# touringmach0.net
KiCad netlist of a schematic drawn in EAGLE
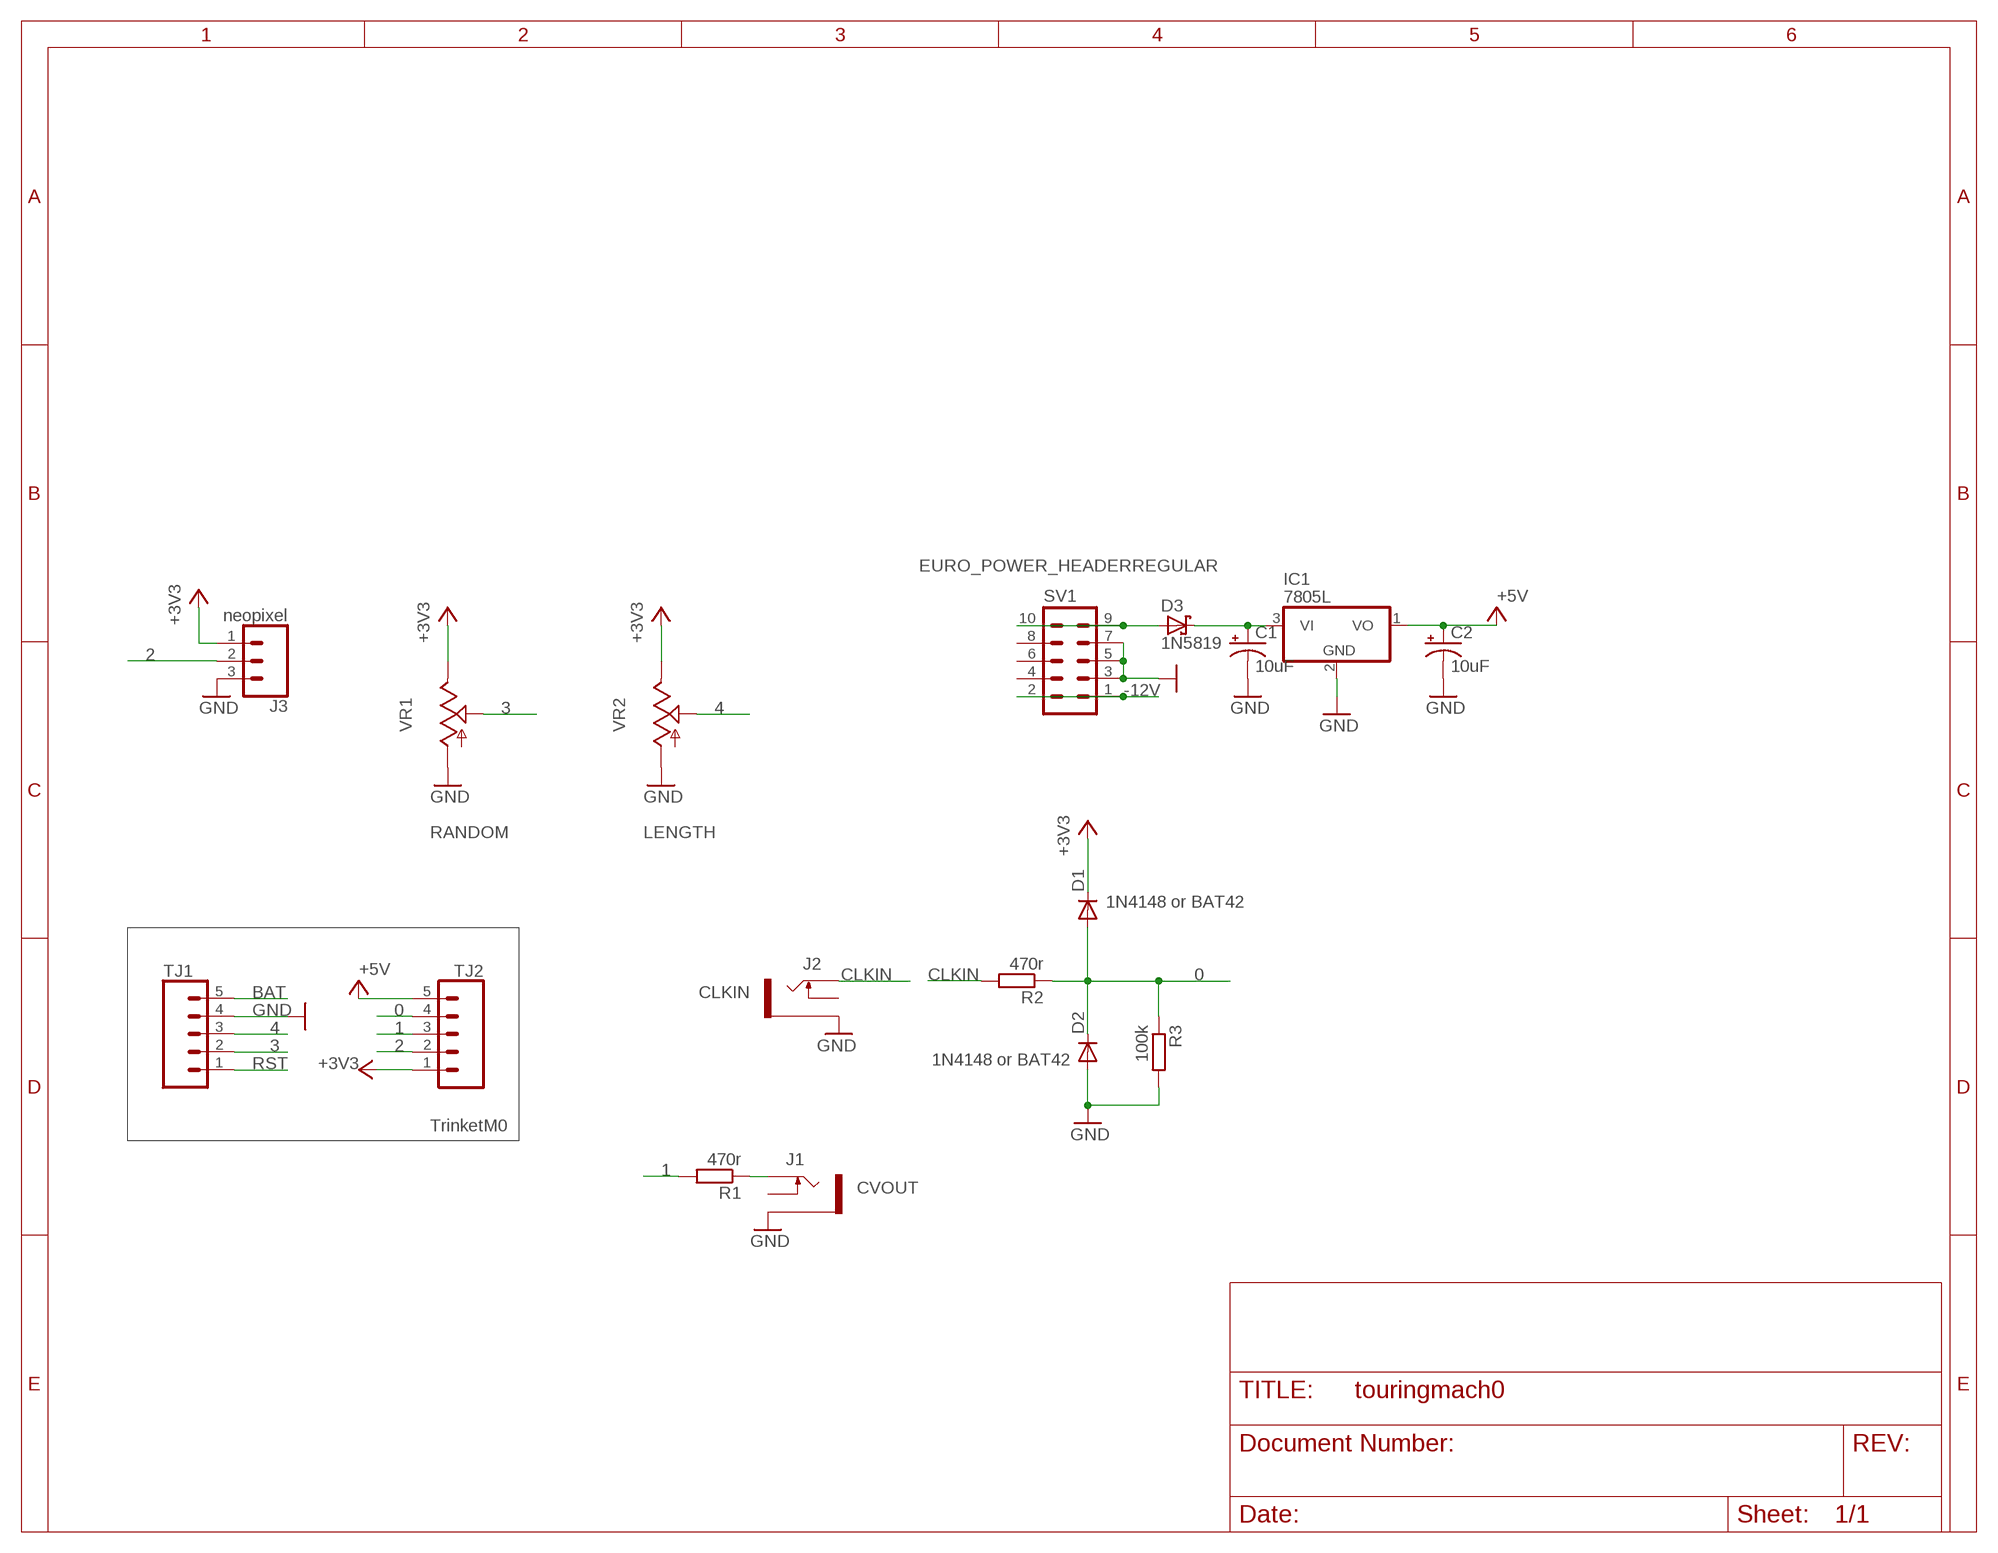
[diagram p0: schematic, sheet 1]

(export (version "E")
  (design (tool "Eeschema 10.0.6"))
  (components
    (comp (ref "C1")
      (value "10uF")
      (footprint "eagle-import:E2,5-6")
      (libsource (lib "eagle-import") (part "CPOL-USE2.5-6"))
    )
    (comp (ref "C2")
      (value "10uF")
      (footprint "eagle-import:E2,5-6")
      (libsource (lib "eagle-import") (part "CPOL-USE2.5-6"))
    )
    (comp (ref "D1")
      (value "1N4148 or BAT42")
      (footprint "eagle-import:DO34-7")
      (libsource (lib "eagle-import") (part "BAT42"))
    )
    (comp (ref "D2")
      (value "1N4148 or BAT42")
      (footprint "eagle-import:DO34-7")
      (libsource (lib "eagle-import") (part "BAT42"))
    )
    (comp (ref "D3")
      (value "1N5819")
      (footprint "eagle-import:DO41-7.6")
      (libsource (lib "eagle-import") (part "1N5819-B"))
    )
    (comp (ref "IC1")
      (value "7805L")
      (footprint "eagle-import:TO92")
      (libsource (lib "eagle-import") (part "78L05"))
    )
    (comp (ref "J1")
      (value "THONKICONNNEW")
      (footprint "eagle-import:WQP-PJ301M-12_JACK")
      (libsource (lib "eagle-import") (part "THONKICONNNEW"))
    )
    (comp (ref "J2")
      (value "THONKICONNNEW")
      (footprint "eagle-import:WQP-PJ301M-12_JACK")
      (libsource (lib "eagle-import") (part "THONKICONNNEW"))
    )
    (comp (ref "J3")
      (value "neopixel")
      (footprint "eagle-import:1X03")
      (libsource (lib "eagle-import") (part "CONN_03"))
    )
    (comp (ref "R1")
      (value "470r")
      (footprint "eagle-import:7MM_RESISTOR")
      (libsource (lib "eagle-import") (part "RESISTOR7MM"))
    )
    (comp (ref "R2")
      (value "470r")
      (footprint "eagle-import:7MM_RESISTOR")
      (libsource (lib "eagle-import") (part "RESISTOR7MM"))
    )
    (comp (ref "R3")
      (value "100k")
      (footprint "eagle-import:7MM_RESISTOR")
      (libsource (lib "eagle-import") (part "RESISTOR7MM"))
    )
    (comp (ref "SV1")
      (value "EURO_POWER_HEADERREGULAR")
      (footprint "eagle-import:EURO_POWER_HEADER")
      (libsource (lib "eagle-import") (part "EURO_POWER_HEADERREGULAR"))
    )
    (comp (ref "TJ1")
      (value "CONN_05")
      (footprint "eagle-import:1X05")
      (libsource (lib "eagle-import") (part "CONN_05"))
    )
    (comp (ref "TJ2")
      (value "CONN_05")
      (footprint "eagle-import:1X05")
      (libsource (lib "eagle-import") (part "CONN_05"))
    )
    (comp (ref "VR1")
      (value "9MM_SNAP-IN_POT_")
      (footprint "eagle-import:9MM_SNAP-IN_POT")
      (libsource (lib "eagle-import") (part "9MM_SNAP-IN_POT_"))
    )
    (comp (ref "VR2")
      (value "9MM_SNAP-IN_POT_")
      (footprint "eagle-import:9MM_SNAP-IN_POT")
      (libsource (lib "eagle-import") (part "9MM_SNAP-IN_POT_"))
    )
  )
  (nets
    (net (code "1") (name "+3V3") (class "Default")
      (node (ref "D1") (pin "C") (pinfunction "C_C") (pintype "passive"))
      (node (ref "J3") (pin "1") (pinfunction "1_1") (pintype "passive"))
      (node (ref "TJ2") (pin "1") (pinfunction "1_1") (pintype "passive"))
      (node (ref "VR1") (pin "3") (pinfunction "E_3") (pintype "passive"))
      (node (ref "VR2") (pin "3") (pinfunction "E_3") (pintype "passive"))
    )
    (net (code "2") (name "+5V") (class "Default")
      (node (ref "C2") (pin "+") (pinfunction "+_+") (pintype "passive"))
      (node (ref "IC1") (pin "1") (pinfunction "VO_1") (pintype "passive"))
      (node (ref "TJ2") (pin "5") (pinfunction "5_5") (pintype "passive"))
    )
    (net (code "3") (name "/-12V") (class "Default")
      (node (ref "SV1") (pin "1") (pinfunction "1_1") (pintype "passive"))
      (node (ref "SV1") (pin "2") (pinfunction "2_2") (pintype "passive"))
    )
    (net (code "4") (name "/0") (class "Default")
      (node (ref "D1") (pin "A") (pinfunction "A_A") (pintype "passive"))
      (node (ref "D2") (pin "C") (pinfunction "C_C") (pintype "passive"))
      (node (ref "R2") (pin "1") (pinfunction "1_1") (pintype "passive"))
      (node (ref "R3") (pin "1") (pinfunction "1_1") (pintype "passive"))
      (node (ref "TJ2") (pin "4") (pinfunction "4_4") (pintype "passive"))
    )
    (net (code "5") (name "/1") (class "Default")
      (node (ref "R1") (pin "2") (pinfunction "2_2") (pintype "passive"))
      (node (ref "TJ2") (pin "3") (pinfunction "3_3") (pintype "passive"))
    )
    (net (code "6") (name "/2") (class "Default")
      (node (ref "J3") (pin "2") (pinfunction "2_2") (pintype "passive"))
      (node (ref "TJ2") (pin "2") (pinfunction "2_2") (pintype "passive"))
    )
    (net (code "7") (name "/3") (class "Default")
      (node (ref "TJ1") (pin "2") (pinfunction "2_2") (pintype "passive"))
      (node (ref "VR1") (pin "2") (pinfunction "S_2") (pintype "passive"))
    )
    (net (code "8") (name "/4") (class "Default")
      (node (ref "TJ1") (pin "3") (pinfunction "3_3") (pintype "passive"))
      (node (ref "VR2") (pin "2") (pinfunction "S_2") (pintype "passive"))
    )
    (net (code "9") (name "/BAT") (class "Default")
      (node (ref "TJ1") (pin "5") (pinfunction "5_5") (pintype "passive"))
    )
    (net (code "10") (name "/CLKIN") (class "Default")
      (node (ref "J2") (pin "P$1_TIP") (pinfunction "TIP_P$1_TIP") (pintype "passive"))
      (node (ref "R2") (pin "2") (pinfunction "2_2") (pintype "passive"))
    )
    (net (code "11") (name "/RST") (class "Default")
      (node (ref "TJ1") (pin "1") (pinfunction "1_1") (pintype "passive"))
    )
    (net (code "12") (name "GND") (class "Default")
      (node (ref "C1") (pin "-") (pinfunction "-_-") (pintype "passive"))
      (node (ref "C2") (pin "-") (pinfunction "-_-") (pintype "passive"))
      (node (ref "D2") (pin "A") (pinfunction "A_A") (pintype "passive"))
      (node (ref "IC1") (pin "2") (pinfunction "GND_2") (pintype "passive"))
      (node (ref "J1") (pin "P$3_SLEEVE") (pinfunction "SLEEVE_P$3_SLEEVE") (pintype "passive"))
      (node (ref "J2") (pin "P$3_SLEEVE") (pinfunction "SLEEVE_P$3_SLEEVE") (pintype "passive"))
      (node (ref "J3") (pin "3") (pinfunction "3_3") (pintype "passive"))
      (node (ref "R3") (pin "2") (pinfunction "2_2") (pintype "passive"))
      (node (ref "SV1") (pin "3") (pinfunction "3_3") (pintype "passive"))
      (node (ref "SV1") (pin "5") (pinfunction "5_5") (pintype "passive"))
      (node (ref "SV1") (pin "7") (pinfunction "7_7") (pintype "passive"))
      (node (ref "TJ1") (pin "4") (pinfunction "4_4") (pintype "passive"))
      (node (ref "VR1") (pin "1") (pinfunction "A_1") (pintype "passive"))
      (node (ref "VR2") (pin "1") (pinfunction "A_1") (pintype "passive"))
    )
    (net (code "13") (name "Net-(D3-PadA)") (class "Default")
      (node (ref "D3") (pin "A") (pinfunction "A_A") (pintype "passive"))
      (node (ref "SV1") (pin "10") (pinfunction "10_10") (pintype "passive"))
      (node (ref "SV1") (pin "9") (pinfunction "9_9") (pintype "passive"))
    )
    (net (code "14") (name "Net-(IC1-VI)") (class "Default")
      (node (ref "C1") (pin "+") (pinfunction "+_+") (pintype "passive"))
      (node (ref "D3") (pin "C") (pinfunction "C_C") (pintype "passive"))
      (node (ref "IC1") (pin "3") (pinfunction "VI_3") (pintype "input"))
    )
    (net (code "15") (name "Net-(J1-TIP)") (class "Default")
      (node (ref "J1") (pin "P$1_TIP") (pinfunction "TIP_P$1_TIP") (pintype "passive"))
      (node (ref "R1") (pin "1") (pinfunction "1_1") (pintype "passive"))
    )
    (net (code "16") (name "unconnected-(J1-SWITCH-PadP$2_SWITCH)") (class "Default")
      (node (ref "J1") (pin "P$2_SWITCH") (pinfunction "SWITCH_P$2_SWITCH") (pintype "passive"))
    )
    (net (code "17") (name "unconnected-(J2-SWITCH-PadP$2_SWITCH)") (class "Default")
      (node (ref "J2") (pin "P$2_SWITCH") (pinfunction "SWITCH_P$2_SWITCH") (pintype "passive"))
    )
    (net (code "18") (name "unconnected-(SV1-Pad4)") (class "Default")
      (node (ref "SV1") (pin "4") (pinfunction "4_4") (pintype "passive"))
    )
    (net (code "19") (name "unconnected-(SV1-Pad6)") (class "Default")
      (node (ref "SV1") (pin "6") (pinfunction "6_6") (pintype "passive"))
    )
    (net (code "20") (name "unconnected-(SV1-Pad8)") (class "Default")
      (node (ref "SV1") (pin "8") (pinfunction "8_8") (pintype "passive"))
    )
  )
)
